# PROC099B_CAN_Interface.net
KiCad netlist of a schematic drawn in Altium Designer
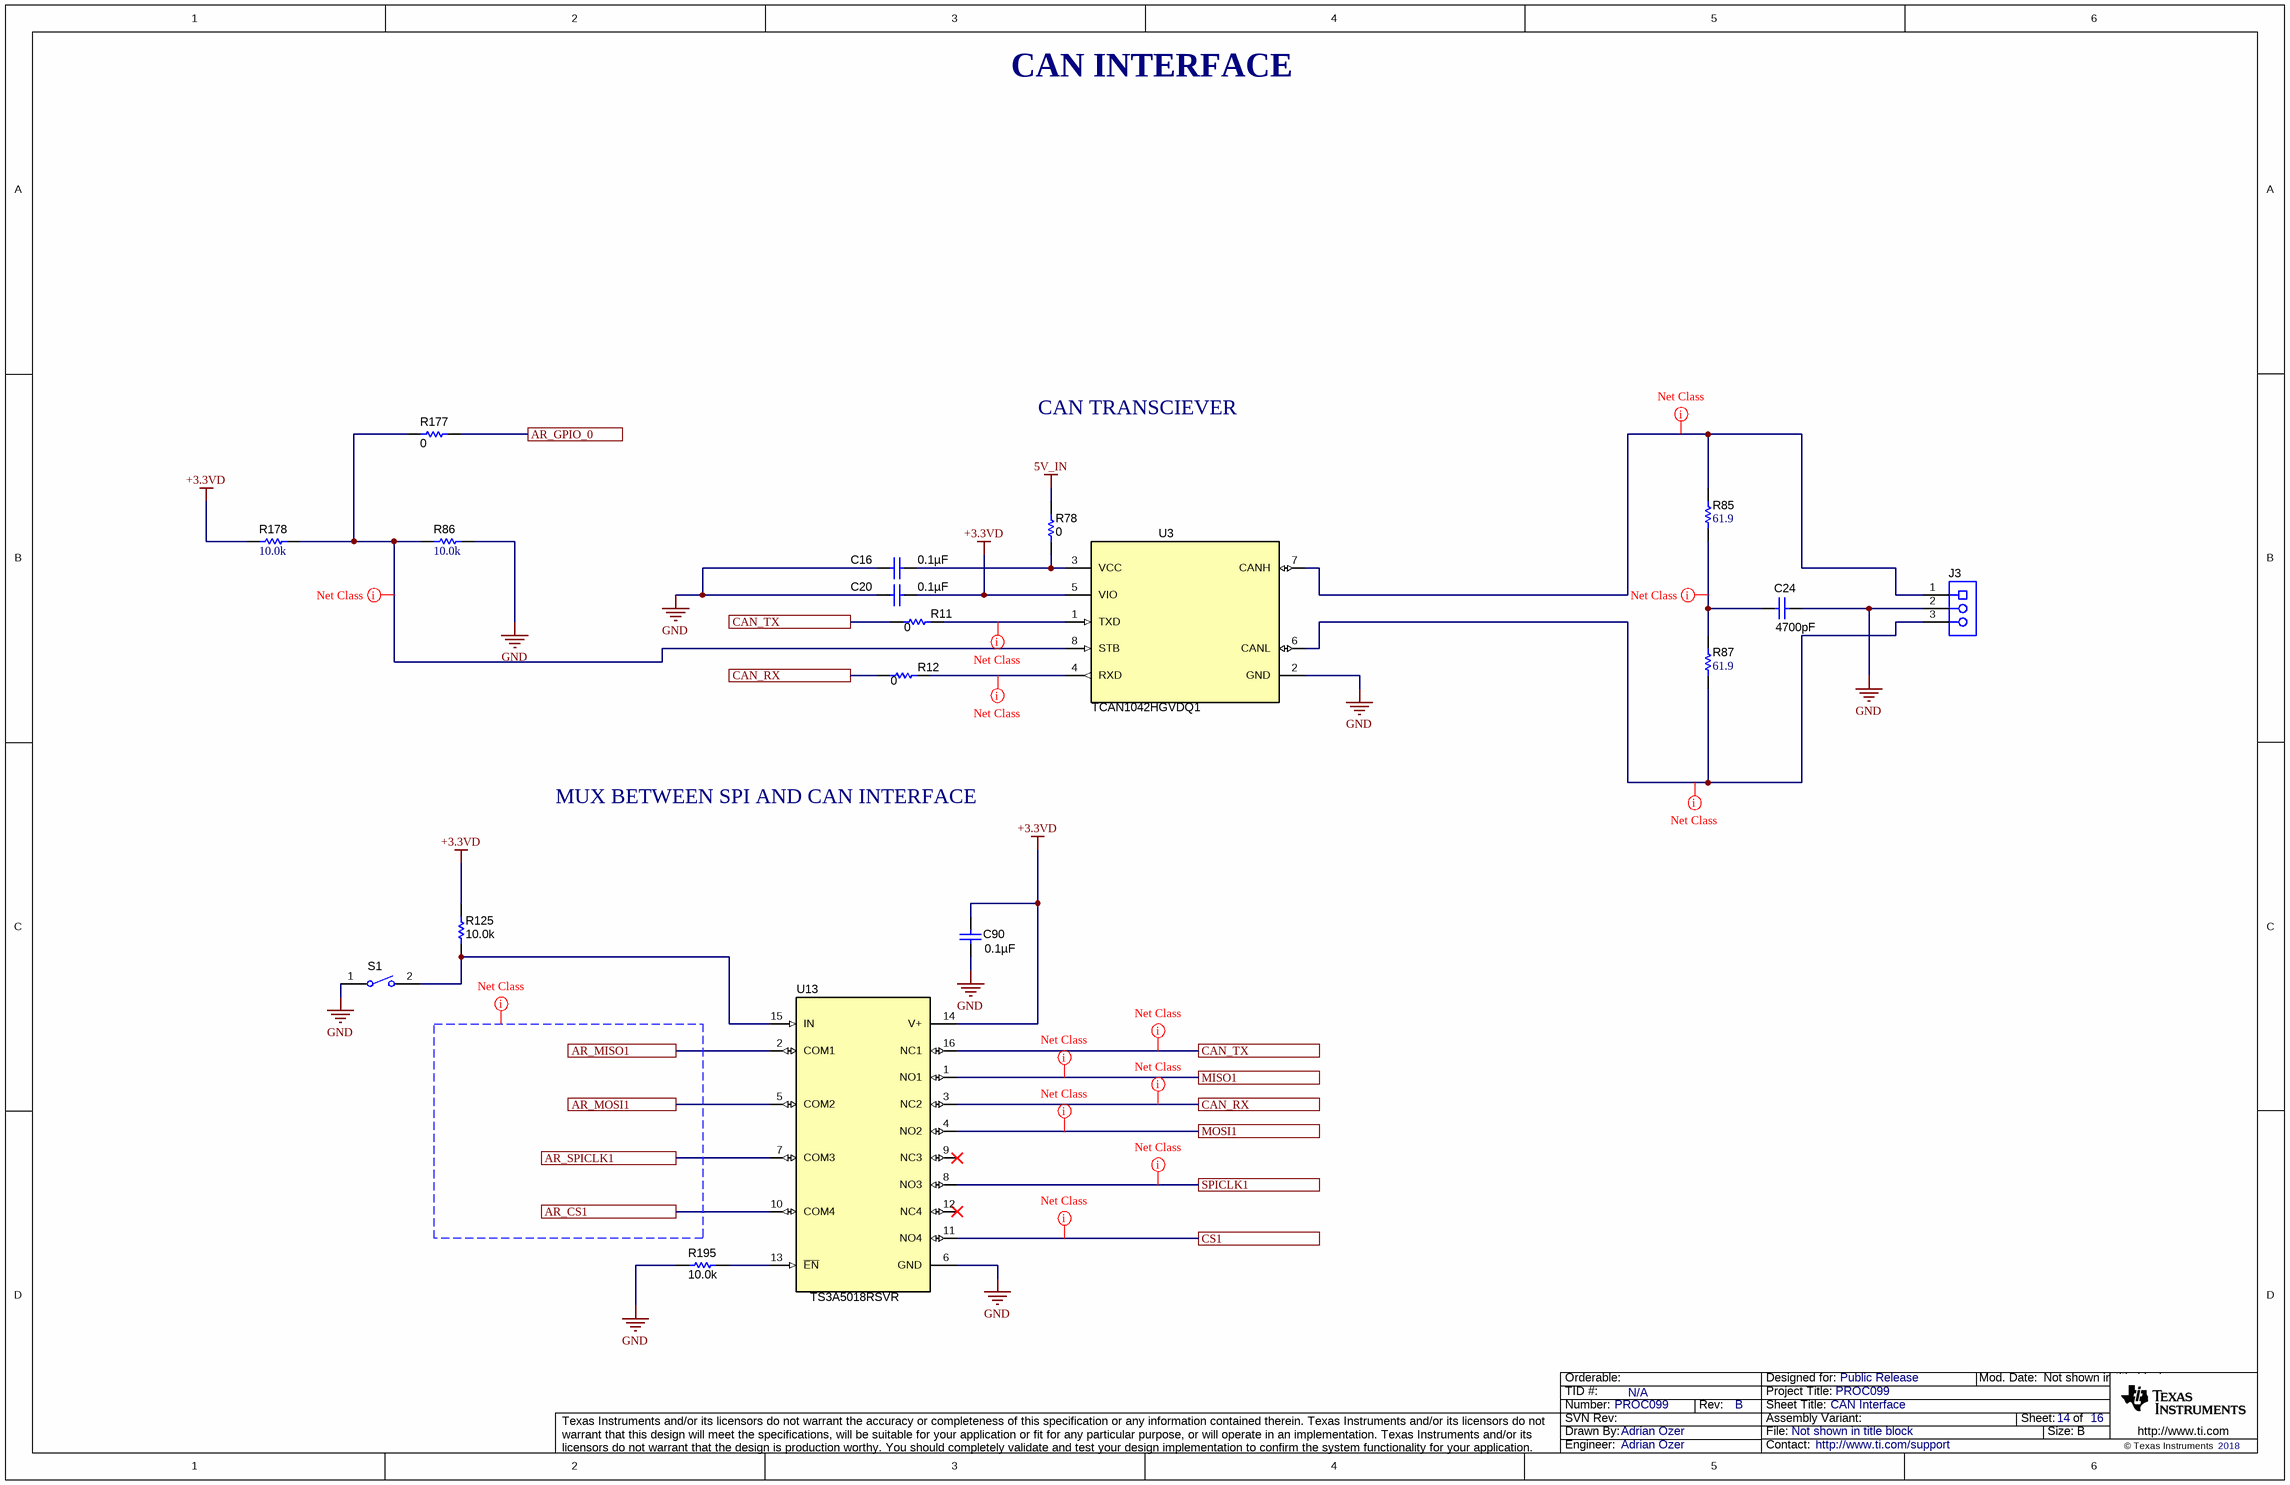
[diagram p0: PROC099B_CAN Interface.SchDoc]

(export (version "E")
  (design (tool "Eeschema 10.0.6"))
  (components
    (comp (ref "C16")
      (value "C0402C104K8RACTU")
      (footprint "0402L")
      (description "CAP, CERM, 0.1 µF, 10 V,+/- 10%, X7R, 0402")
      (fields (field (name "MANUFACTURER") "Kemet") (field (name "VALUEDISPLAYED") "0.1µF"))
      (libsource (lib "Altium Vault - TI") (part "Capacitor"))
    )
    (comp (ref "C20")
      (value "C0402C104K8RACTU")
      (footprint "0402L")
      (description "CAP, CERM, 0.1 µF, 10 V,+/- 10%, X7R, 0402")
      (fields (field (name "MANUFACTURER") "Kemet") (field (name "VALUEDISPLAYED") "0.1µF"))
      (libsource (lib "Altium Vault - TI") (part "Capacitor"))
    )
    (comp (ref "C24")
      (value "GCM155R71H472KA37D")
      (footprint "0402S")
      (description "CAP, CERM, 4700 pF, 50 V, +/- 10%, X7R, AEC-Q200 Grade 1, 0402")
      (fields
        (field (name "MANUFACTURER") "MuRata")
        (field (name "VALUEDISPLAYED") "4700pF")
        (field (name "PUBLISHER") "Texas Instruments")
      )
      (libsource (lib "Altium Vault - TI") (part "Capacitor"))
    )
    (comp (ref "C90")
      (value "C0402C104K8RACTU")
      (footprint "0402L")
      (description "CAP, CERM, 0.1 µF, 10 V,+/- 10%, X7R, 0402")
      (fields (field (name "MANUFACTURER") "Kemet") (field (name "VALUEDISPLAYED") "0.1µF"))
      (libsource (lib "Altium Vault - TI") (part "Capacitor"))
    )
    (comp (ref "J3")
      (value "OSTTE030161")
      (footprint "On-Shore_OSTTE030161")
      (description "Terminal Block, 3.5mm, 3x1, Tin, R/A, TH")
      (fields
        (field (name "MANUFACTURER") "On-Shore Technology")
        (field (name "PUBLISHER") "Texas Instruments")
      )
      (libsource (lib "Altium Vault - TI") (part "Receptacle_3x1"))
    )
    (comp (ref "R11")
      (value "ERJ-2GE0R00X")
      (footprint "0402L")
      (description "RES, 0, 5%, 0.063 W, 0402")
      (fields
        (field (name "MANUFACTURER") "Panasonic")
        (field (name "VALUEDISPLAYED") "0")
        (field (name "PUBLISHER") "Texas Instruments")
      )
      (libsource (lib "Altium Vault - TI") (part "CMP-0026992-2"))
    )
    (comp (ref "R12")
      (value "ERJ-2GE0R00X")
      (footprint "0402L")
      (description "RES, 0, 5%, 0.063 W, 0402")
      (fields
        (field (name "MANUFACTURER") "Panasonic")
        (field (name "VALUEDISPLAYED") "0")
        (field (name "PUBLISHER") "Texas Instruments")
      )
      (libsource (lib "Altium Vault - TI") (part "CMP-0026992-2"))
    )
    (comp (ref "R78")
      (value "ERJ-2GE0R00X")
      (footprint "0402L")
      (description "RES, 0, 5%, 0.063 W, 0402")
      (fields
        (field (name "MANUFACTURER") "Panasonic")
        (field (name "VALUEDISPLAYED") "0")
        (field (name "PUBLISHER") "Texas Instruments")
      )
      (libsource (lib "Altium Vault - TI") (part "CMP-0026992-2"))
    )
    (comp (ref "R85")
      (value "CRCW040261R9FKED")
      (footprint "0402L")
      (description "RES, 61.9, 1%, 0.063 W, AEC-Q200 Grade 0, 0402")
      (fields (field (name "MANUFACTURER") "Vishay-Dale") (field (name "VALUEDISPLAYED") "61.9"))
      (libsource (lib "Altium Vault - TI") (part "Resistor"))
    )
    (comp (ref "R86")
      (value "CRCW040210K0FKED")
      (footprint "0402L")
      (description "RES, 10.0 k, 1%, 0.063 W, AEC-Q200 Grade 0, 0402")
      (fields (field (name "MANUFACTURER") "Vishay-Dale") (field (name "VALUEDISPLAYED") "10.0k"))
      (libsource (lib "Altium Vault - TI") (part "Resistor"))
    )
    (comp (ref "R87")
      (value "CRCW040261R9FKED")
      (footprint "0402L")
      (description "RES, 61.9, 1%, 0.063 W, AEC-Q200 Grade 0, 0402")
      (fields (field (name "MANUFACTURER") "Vishay-Dale") (field (name "VALUEDISPLAYED") "61.9"))
      (libsource (lib "Altium Vault - TI") (part "Resistor"))
    )
    (comp (ref "R125")
      (value "CRCW040210K0FKED")
      (footprint "0402L")
      (description "RES, 10.0 k, 1%, 0.063 W, 0402")
      (fields
        (field (name "MANUFACTURER") "Vishay-Dale")
        (field (name "VALUEDISPLAYED") "10.0k")
        (field (name "PUBLISHER") "Texas Instruments")
      )
      (libsource (lib "Altium Vault - TI") (part "CMP-0025958-2"))
    )
    (comp (ref "R177")
      (value "ERJ-2GE0R00X")
      (footprint "0402L")
      (description "RES, 0, 5%, 0.063 W, 0402")
      (fields
        (field (name "MANUFACTURER") "Panasonic")
        (field (name "VALUEDISPLAYED") "0")
        (field (name "PUBLISHER") "Texas Instruments")
      )
      (libsource (lib "Altium Vault - TI") (part "CMP-0026992-2"))
    )
    (comp (ref "R178")
      (value "CRCW040210K0FKED")
      (footprint "0402L")
      (description "RES, 10.0 k, 1%, 0.063 W, AEC-Q200 Grade 0, 0402")
      (fields (field (name "MANUFACTURER") "Vishay-Dale") (field (name "VALUEDISPLAYED") "10.0k"))
      (libsource (lib "Altium Vault - TI") (part "Resistor"))
    )
    (comp (ref "R195")
      (value "CRCW040210K0FKED")
      (footprint "0402L")
      (description "RES, 10.0 k, 1%, 0.063 W, 0402")
      (fields
        (field (name "MANUFACTURER") "Vishay-Dale")
        (field (name "VALUEDISPLAYED") "10.0k")
        (field (name "PUBLISHER") "Texas Instruments")
      )
      (libsource (lib "Altium Vault - TI") (part "CMP-0025958-2"))
    )
    (comp (ref "S1")
      (value "CHS-01TB")
      (footprint "SW_CHS-01TB")
      (description "Switch, Slide, SPST, Top Slide, SMT")
      (fields
        (field (name "MANUFACTURER") "Copal Electronics")
        (field (name "PUBLISHER") "Texas Instruments")
      )
      (libsource (lib "Altium Vault - TI") (part "SW_SPST-single"))
    )
    (comp (ref "U3")
      (value "TCAN1042HGVDQ1")
      (footprint "D0008A_L")
      (description "Automotive Fault Protected CAN Transceiver With Flexible Data-Rate, D0008A (SOIC-8)")
      (fields
        (field (name "PARTNUMBER") "TCAN1042HGVDQ1")
        (field (name "MANUFACTURER") "Texas Instruments")
        (field (name "ALTERNATE PARTNUMBER") "TCAN1042HGVDRQ1")
        (field (name "PUBLISHER") "Texas Instruments")
      )
      (libsource (lib "Altium Vault - TI") (part "TCAN1042_V"))
    )
    (comp (ref "U13")
      (value "TS3A5018RSVR")
      (footprint "RSV0016A")
      (description "10-Ohm Quad SPDT Analog Switch, RSV0016A (UQFN-16)")
      (fields
        (field (name "MANUFACTURER") "Texas Instruments")
        (field (name "PARTNUMBER") "TS3A5018RSVR")
        (field (name "PUBLISHER") "Texas Instruments")
      )
      (libsource (lib "Altium Vault - TI") (part "CMP-0067415-1"))
    )
  )
  (nets
    (net (code "1") (name "+3.3VD") (class "Default")
      (node (ref "C20") (pin "2") (pinfunction "2_2") (pintype "passive"))
      (node (ref "C90") (pin "2") (pinfunction "2_2") (pintype "passive"))
      (node (ref "R125") (pin "2") (pinfunction "2_2") (pintype "passive"))
      (node (ref "R178") (pin "1") (pinfunction "1_1") (pintype "passive"))
      (node (ref "U13") (pin "14") (pinfunction "V+_14") (pintype "power_in"))
      (node (ref "U3") (pin "5") (pinfunction "VIO_5") (pintype "power_in"))
    )
    (net (code "2") (name "/AR_CS1") (class "Default")
      (node (ref "U13") (pin "10") (pinfunction "COM4_10") (pintype "bidirectional"))
    )
    (net (code "3") (name "/AR_GPIO_0") (class "Default")
      (node (ref "R177") (pin "2") (pinfunction "2_2") (pintype "passive"))
    )
    (net (code "4") (name "/AR_MISO1") (class "Default")
      (node (ref "U13") (pin "2") (pinfunction "COM1_2") (pintype "bidirectional"))
    )
    (net (code "5") (name "/AR_MOSI1") (class "Default")
      (node (ref "U13") (pin "5") (pinfunction "COM2_5") (pintype "bidirectional"))
    )
    (net (code "6") (name "/AR_SPICLK1") (class "Default")
      (node (ref "U13") (pin "7") (pinfunction "COM3_7") (pintype "bidirectional"))
    )
    (net (code "7") (name "/CAN_RX") (class "Default")
      (node (ref "R12") (pin "1") (pinfunction "1_1") (pintype "passive"))
      (node (ref "U13") (pin "3") (pinfunction "NC2_3") (pintype "bidirectional"))
    )
    (net (code "8") (name "/CAN_TX") (class "Default")
      (node (ref "R11") (pin "1") (pinfunction "1_1") (pintype "passive"))
      (node (ref "U13") (pin "16") (pinfunction "NC1_16") (pintype "bidirectional"))
    )
    (net (code "9") (name "/CS1") (class "Default")
      (node (ref "U13") (pin "11") (pinfunction "NO4_11") (pintype "bidirectional"))
    )
    (net (code "10") (name "/MISO1") (class "Default")
      (node (ref "U13") (pin "1") (pinfunction "NO1_1") (pintype "bidirectional"))
    )
    (net (code "11") (name "/MOSI1") (class "Default")
      (node (ref "U13") (pin "4") (pinfunction "NO2_4") (pintype "bidirectional"))
    )
    (net (code "12") (name "/SPICLK1") (class "Default")
      (node (ref "U13") (pin "8") (pinfunction "NO3_8") (pintype "bidirectional"))
    )
    (net (code "13") (name "5V_IN") (class "Default")
      (node (ref "R78") (pin "2") (pinfunction "2_2") (pintype "passive"))
    )
    (net (code "14") (name "GND") (class "Default")
      (node (ref "C16") (pin "1") (pinfunction "1_1") (pintype "passive"))
      (node (ref "C20") (pin "1") (pinfunction "1_1") (pintype "passive"))
      (node (ref "C24") (pin "1") (pinfunction "1_1") (pintype "passive"))
      (node (ref "C90") (pin "1") (pinfunction "1_1") (pintype "passive"))
      (node (ref "J3") (pin "2") (pinfunction "2_2") (pintype "passive"))
      (node (ref "R195") (pin "2") (pinfunction "2_2") (pintype "passive"))
      (node (ref "R86") (pin "2") (pinfunction "2_2") (pintype "passive"))
      (node (ref "S1") (pin "1") (pinfunction "1_1") (pintype "passive"))
      (node (ref "U13") (pin "6") (pinfunction "GND_6") (pintype "power_in"))
      (node (ref "U3") (pin "2") (pinfunction "GND_2") (pintype "power_in"))
    )
    (net (code "15") (name "Net-(C24-Pad2)") (class "Default")
      (node (ref "C24") (pin "2") (pinfunction "2_2") (pintype "passive"))
      (node (ref "R85") (pin "1") (pinfunction "1_1") (pintype "passive"))
      (node (ref "R87") (pin "2") (pinfunction "2_2") (pintype "passive"))
    )
    (net (code "16") (name "Net-(U3-CANH)") (class "Default")
      (node (ref "J3") (pin "1") (pinfunction "1_1") (pintype "passive"))
      (node (ref "R85") (pin "2") (pinfunction "2_2") (pintype "passive"))
      (node (ref "U3") (pin "7") (pinfunction "CANH_7") (pintype "bidirectional"))
    )
    (net (code "17") (name "Net-(U3-CANL)") (class "Default")
      (node (ref "J3") (pin "3") (pinfunction "3_3") (pintype "passive"))
      (node (ref "R87") (pin "1") (pinfunction "1_1") (pintype "passive"))
      (node (ref "U3") (pin "6") (pinfunction "CANL_6") (pintype "bidirectional"))
    )
    (net (code "18") (name "Net-(U3-RXD)") (class "Default")
      (node (ref "R12") (pin "2") (pinfunction "2_2") (pintype "passive"))
      (node (ref "U3") (pin "4") (pinfunction "RXD_4") (pintype "output"))
    )
    (net (code "19") (name "Net-(U3-STB)") (class "Default")
      (node (ref "R177") (pin "1") (pinfunction "1_1") (pintype "passive"))
      (node (ref "R178") (pin "2") (pinfunction "2_2") (pintype "passive"))
      (node (ref "R86") (pin "1") (pinfunction "1_1") (pintype "passive"))
      (node (ref "U3") (pin "8") (pinfunction "STB_8") (pintype "input"))
    )
    (net (code "20") (name "Net-(U3-TXD)") (class "Default")
      (node (ref "R11") (pin "2") (pinfunction "2_2") (pintype "passive"))
      (node (ref "U3") (pin "1") (pinfunction "TXD_1") (pintype "input"))
    )
    (net (code "21") (name "Net-(U3-VCC)") (class "Default")
      (node (ref "C16") (pin "2") (pinfunction "2_2") (pintype "passive"))
      (node (ref "R78") (pin "1") (pinfunction "1_1") (pintype "passive"))
      (node (ref "U3") (pin "3") (pinfunction "VCC_3") (pintype "power_in"))
    )
    (net (code "22") (name "Net-(U13-EN)") (class "Default")
      (node (ref "R195") (pin "1") (pinfunction "1_1") (pintype "passive"))
      (node (ref "U13") (pin "13") (pinfunction "EN_13") (pintype "input"))
    )
    (net (code "23") (name "Net-(U13-IN)") (class "Default")
      (node (ref "R125") (pin "1") (pinfunction "1_1") (pintype "passive"))
      (node (ref "S1") (pin "2") (pinfunction "2_2") (pintype "passive"))
      (node (ref "U13") (pin "15") (pinfunction "IN_15") (pintype "input"))
    )
    (net (code "24") (name "unconnected-(U13-NC3-Pad9)") (class "Default")
      (node (ref "U13") (pin "9") (pinfunction "NC3_9") (pintype "bidirectional+no_connect"))
    )
    (net (code "25") (name "unconnected-(U13-NC4-Pad12)") (class "Default")
      (node (ref "U13") (pin "12") (pinfunction "NC4_12") (pintype "bidirectional+no_connect"))
    )
  )
)
